# Steuerung.net
KiCad netlist of a schematic drawn in EAGLE
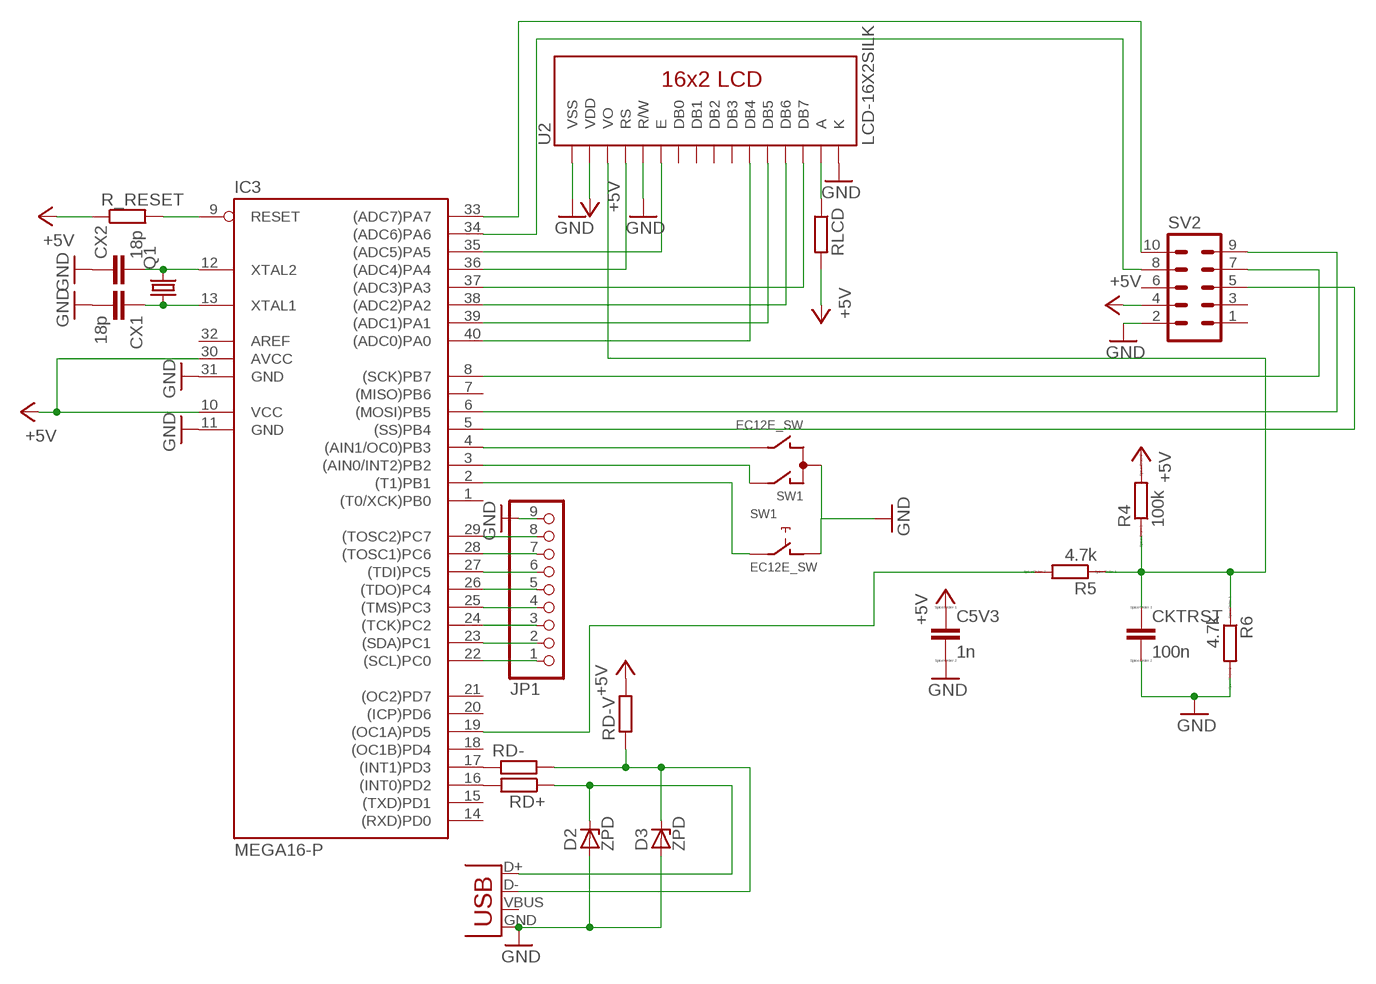
[diagram p0: schematic, sheet 1]

(export (version "E")
  (design (tool "Eeschema 10.0.6"))
  (components
    (comp (ref "C5V3")
      (value "1n")
      (footprint "eagle-import:C1206K")
      (libsource (lib "eagle-import") (part "C-EUC1206K"))
    )
    (comp (ref "CKTRST")
      (value "100n")
      (footprint "eagle-import:C1206K")
      (libsource (lib "eagle-import") (part "C-EUC1206K"))
    )
    (comp (ref "CX1")
      (value "18p")
      (footprint "eagle-import:C2.5-3")
      (libsource (lib "eagle-import") (part "C2,5-3"))
    )
    (comp (ref "CX2")
      (value "18p")
      (footprint "eagle-import:C2.5-3")
      (libsource (lib "eagle-import") (part "C2,5-3"))
    )
    (comp (ref "D2")
      (value "ZPD")
      (footprint "eagle-import:DO35Z10")
      (libsource (lib "eagle-import") (part "ZPD"))
    )
    (comp (ref "D3")
      (value "ZPD")
      (footprint "eagle-import:DO35Z10")
      (libsource (lib "eagle-import") (part "ZPD"))
    )
    (comp (ref "IC3")
      (value "MEGA16-P")
      (footprint "eagle-import:DIL40")
      (fields (field (name "MPN") "ATMEGA16-16PU") (field (name "MF") "ATMEL"))
      (libsource (lib "eagle-import") (part "MEGA16-P"))
    )
    (comp (ref "JP1")
      (value "PINHD-1X9")
      (footprint "eagle-import:1X09")
      (libsource (lib "eagle-import") (part "PINHD-1X9"))
    )
    (comp (ref "JP2")
      (value "USBPTH-VERTICAL")
      (footprint "eagle-import:USB-B-PTH-VERTICAL")
      (libsource (lib "eagle-import") (part "USBPTH-VERTICAL"))
    )
    (comp (ref "Q1")
      (value "CRYSTALHC18U-V")
      (footprint "eagle-import:HC18U-V")
      (libsource (lib "eagle-import") (part "CRYSTALHC18U-V"))
    )
    (comp (ref "R4")
      (value "100k")
      (footprint "eagle-import:R1206W")
      (libsource (lib "eagle-import") (part "resistor_R-EU_R1206W"))
    )
    (comp (ref "R5")
      (value "4.7k")
      (footprint "eagle-import:R1206W")
      (libsource (lib "eagle-import") (part "resistor_R-EU_R1206W"))
    )
    (comp (ref "R6")
      (value "4.7k")
      (footprint "eagle-import:R1206W")
      (libsource (lib "eagle-import") (part "resistor_R-EU_R1206W"))
    )
    (comp (ref "RD+")
      (value "R-EU_0309/12")
      (footprint "eagle-import:0309_12")
      (libsource (lib "eagle-import") (part "R-EU_0309/12"))
    )
    (comp (ref "RD-")
      (value "R-EU_0309/12")
      (footprint "eagle-import:0309_12")
      (libsource (lib "eagle-import") (part "R-EU_0309/12"))
    )
    (comp (ref "RD-V")
      (value "R-EU_0309/12")
      (footprint "eagle-import:0309_12")
      (libsource (lib "eagle-import") (part "R-EU_0309/12"))
    )
    (comp (ref "RLCD")
      (value "R-EU_0309/12")
      (footprint "eagle-import:0309_12")
      (libsource (lib "eagle-import") (part "R-EU_0309/12"))
    )
    (comp (ref "R_RESET")
      (value "R-EU_R1206W")
      (footprint "eagle-import:R1206W")
      (libsource (lib "eagle-import") (part "R-EU_R1206W"))
    )
    (comp (ref "SV2")
      (value "ML10")
      (footprint "eagle-import:ML10")
      (libsource (lib "eagle-import") (part "ML10"))
    )
    (comp (ref "SW1")
      (value "EC12E_SW")
      (footprint "eagle-import:ALPS_EC12E_SW")
      (fields (field (name "MPN") "EC12E2424407"))
      (libsource (lib "eagle-import") (part "EC12E_SW"))
    )
    (comp (ref "U2")
      (value "LCD-16X2SILK")
      (footprint "eagle-import:LCD-16X2")
      (libsource (lib "eagle-import") (part "LCD-16X2SILK"))
    )
  )
  (nets
    (net (code "1") (name "+5V") (class "Default")
      (node (ref "C5V3") (pin "1") (pinfunction "1_1") (pintype "passive"))
      (node (ref "IC3") (pin "10") (pinfunction "VCC_10") (pintype "power_in"))
      (node (ref "IC3") (pin "30") (pinfunction "AVCC_30") (pintype "power_in"))
      (node (ref "R4") (pin "2") (pinfunction "2_2") (pintype "passive"))
      (node (ref "RD-V") (pin "2") (pinfunction "2_2") (pintype "passive"))
      (node (ref "RLCD") (pin "2") (pinfunction "2_2") (pintype "passive"))
      (node (ref "R_RESET") (pin "1") (pinfunction "1_1") (pintype "passive"))
      (node (ref "SV2") (pin "4") (pinfunction "4_4") (pintype "passive"))
      (node (ref "U2") (pin "2") (pinfunction "VDD_2") (pintype "power_in"))
    )
    (net (code "2") (name "GND") (class "Default")
      (node (ref "C5V3") (pin "2") (pinfunction "2_2") (pintype "passive"))
      (node (ref "CKTRST") (pin "2") (pinfunction "2_2") (pintype "passive"))
      (node (ref "CX1") (pin "2") (pinfunction "2_2") (pintype "passive"))
      (node (ref "CX2") (pin "1") (pinfunction "1_1") (pintype "passive"))
      (node (ref "D2") (pin "A") (pinfunction "A_A") (pintype "passive"))
      (node (ref "D3") (pin "A") (pinfunction "A_A") (pintype "passive"))
      (node (ref "IC3") (pin "11") (pinfunction "GND_11") (pintype "power_in"))
      (node (ref "IC3") (pin "31") (pinfunction "GND_31") (pintype "power_in"))
      (node (ref "JP1") (pin "9") (pinfunction "9_9") (pintype "passive"))
      (node (ref "JP2") (pin "GND") (pinfunction "GND_GND") (pintype "bidirectional"))
      (node (ref "R6") (pin "2") (pinfunction "2_2") (pintype "passive"))
      (node (ref "SV2") (pin "2") (pinfunction "2_2") (pintype "passive"))
      (node (ref "SW1") (pin "C") (pinfunction "C_C") (pintype "passive"))
      (node (ref "SW1") (pin "D") (pinfunction "1_D") (pintype "passive"))
      (node (ref "U2") (pin "1") (pinfunction "VSS_1") (pintype "power_in"))
      (node (ref "U2") (pin "16") (pinfunction "K_16") (pintype "power_in"))
      (node (ref "U2") (pin "5") (pinfunction "R/W_5") (pintype "input"))
    )
    (net (code "3") (name "Net-(D2-PadC)") (class "Default")
      (node (ref "D2") (pin "C") (pinfunction "C_C") (pintype "passive"))
      (node (ref "JP2") (pin "D+") (pinfunction "D+_D+") (pintype "bidirectional"))
      (node (ref "RD+") (pin "1") (pinfunction "1_1") (pintype "passive"))
    )
    (net (code "4") (name "Net-(D3-PadC)") (class "Default")
      (node (ref "D3") (pin "C") (pinfunction "C_C") (pintype "passive"))
      (node (ref "JP2") (pin "D-") (pinfunction "D-_D-") (pintype "bidirectional"))
      (node (ref "RD-") (pin "2") (pinfunction "2_2") (pintype "passive"))
      (node (ref "RD-V") (pin "1") (pinfunction "1_1") (pintype "passive"))
    )
    (net (code "5") (name "Net-(IC3-(ADC0)PA0)") (class "Default")
      (node (ref "IC3") (pin "40") (pinfunction "(ADC0)PA0_40") (pintype "bidirectional"))
      (node (ref "U2") (pin "11") (pinfunction "DB4_11") (pintype "bidirectional"))
    )
    (net (code "6") (name "Net-(IC3-(ADC1)PA1)") (class "Default")
      (node (ref "IC3") (pin "39") (pinfunction "(ADC1)PA1_39") (pintype "bidirectional"))
      (node (ref "U2") (pin "12") (pinfunction "DB5_12") (pintype "bidirectional"))
    )
    (net (code "7") (name "Net-(IC3-(ADC2)PA2)") (class "Default")
      (node (ref "IC3") (pin "38") (pinfunction "(ADC2)PA2_38") (pintype "bidirectional"))
      (node (ref "U2") (pin "13") (pinfunction "DB6_13") (pintype "bidirectional"))
    )
    (net (code "8") (name "Net-(IC3-(ADC3)PA3)") (class "Default")
      (node (ref "IC3") (pin "37") (pinfunction "(ADC3)PA3_37") (pintype "bidirectional"))
      (node (ref "U2") (pin "14") (pinfunction "DB7_14") (pintype "bidirectional"))
    )
    (net (code "9") (name "Net-(IC3-(ADC4)PA4)") (class "Default")
      (node (ref "IC3") (pin "36") (pinfunction "(ADC4)PA4_36") (pintype "bidirectional"))
      (node (ref "U2") (pin "4") (pinfunction "RS_4") (pintype "input"))
    )
    (net (code "10") (name "Net-(IC3-(ADC5)PA5)") (class "Default")
      (node (ref "IC3") (pin "35") (pinfunction "(ADC5)PA5_35") (pintype "bidirectional"))
      (node (ref "U2") (pin "6") (pinfunction "E_6") (pintype "input"))
    )
    (net (code "11") (name "Net-(IC3-(ADC6)PA6)") (class "Default")
      (node (ref "IC3") (pin "34") (pinfunction "(ADC6)PA6_34") (pintype "bidirectional"))
      (node (ref "SV2") (pin "8") (pinfunction "8_8") (pintype "passive"))
    )
    (net (code "12") (name "Net-(IC3-(ADC7)PA7)") (class "Default")
      (node (ref "IC3") (pin "33") (pinfunction "(ADC7)PA7_33") (pintype "bidirectional"))
      (node (ref "SV2") (pin "10") (pinfunction "10_10") (pintype "passive"))
    )
    (net (code "13") (name "Net-(IC3-(AIN0{slash}INT2)PB2)") (class "Default")
      (node (ref "IC3") (pin "3") (pinfunction "(AIN0/INT2)PB2_3") (pintype "bidirectional"))
      (node (ref "SW1") (pin "A") (pinfunction "A_A") (pintype "passive"))
    )
    (net (code "14") (name "Net-(IC3-(AIN1{slash}OC0)PB3)") (class "Default")
      (node (ref "IC3") (pin "4") (pinfunction "(AIN1/OC0)PB3_4") (pintype "bidirectional"))
      (node (ref "SW1") (pin "B") (pinfunction "B_B") (pintype "passive"))
    )
    (net (code "15") (name "Net-(IC3-(INT0)PD2)") (class "Default")
      (node (ref "IC3") (pin "16") (pinfunction "(INT0)PD2_16") (pintype "bidirectional"))
      (node (ref "RD+") (pin "2") (pinfunction "2_2") (pintype "passive"))
    )
    (net (code "16") (name "Net-(IC3-(INT1)PD3)") (class "Default")
      (node (ref "IC3") (pin "17") (pinfunction "(INT1)PD3_17") (pintype "bidirectional"))
      (node (ref "RD-") (pin "1") (pinfunction "1_1") (pintype "passive"))
    )
    (net (code "17") (name "Net-(IC3-(MOSI)PB5)") (class "Default")
      (node (ref "IC3") (pin "6") (pinfunction "(MOSI)PB5_6") (pintype "bidirectional"))
      (node (ref "SV2") (pin "9") (pinfunction "9_9") (pintype "passive"))
    )
    (net (code "18") (name "Net-(IC3-(OC1A)PD5)") (class "Default")
      (node (ref "IC3") (pin "19") (pinfunction "(OC1A)PD5_19") (pintype "bidirectional"))
      (node (ref "R5") (pin "2") (pinfunction "2_2") (pintype "passive"))
    )
    (net (code "19") (name "Net-(IC3-(SCK)PB7)") (class "Default")
      (node (ref "IC3") (pin "8") (pinfunction "(SCK)PB7_8") (pintype "bidirectional"))
      (node (ref "SV2") (pin "7") (pinfunction "7_7") (pintype "passive"))
    )
    (net (code "20") (name "Net-(IC3-(SCL)PC0)") (class "Default")
      (node (ref "IC3") (pin "22") (pinfunction "(SCL)PC0_22") (pintype "bidirectional"))
      (node (ref "JP1") (pin "1") (pinfunction "1_1") (pintype "passive"))
    )
    (net (code "21") (name "Net-(IC3-(SDA)PC1)") (class "Default")
      (node (ref "IC3") (pin "23") (pinfunction "(SDA)PC1_23") (pintype "bidirectional"))
      (node (ref "JP1") (pin "2") (pinfunction "2_2") (pintype "passive"))
    )
    (net (code "22") (name "Net-(IC3-(SS)PB4)") (class "Default")
      (node (ref "IC3") (pin "5") (pinfunction "(SS)PB4_5") (pintype "bidirectional"))
      (node (ref "SV2") (pin "5") (pinfunction "5_5") (pintype "passive"))
    )
    (net (code "23") (name "Net-(IC3-(T1)PB1)") (class "Default")
      (node (ref "IC3") (pin "2") (pinfunction "(T1)PB1_2") (pintype "bidirectional"))
      (node (ref "SW1") (pin "E") (pinfunction "2_E") (pintype "passive"))
    )
    (net (code "24") (name "Net-(IC3-(TCK)PC2)") (class "Default")
      (node (ref "IC3") (pin "24") (pinfunction "(TCK)PC2_24") (pintype "bidirectional"))
      (node (ref "JP1") (pin "3") (pinfunction "3_3") (pintype "passive"))
    )
    (net (code "25") (name "Net-(IC3-(TDI)PC5)") (class "Default")
      (node (ref "IC3") (pin "27") (pinfunction "(TDI)PC5_27") (pintype "bidirectional"))
      (node (ref "JP1") (pin "6") (pinfunction "6_6") (pintype "passive"))
    )
    (net (code "26") (name "Net-(IC3-(TDO)PC4)") (class "Default")
      (node (ref "IC3") (pin "26") (pinfunction "(TDO)PC4_26") (pintype "bidirectional"))
      (node (ref "JP1") (pin "5") (pinfunction "5_5") (pintype "passive"))
    )
    (net (code "27") (name "Net-(IC3-(TMS)PC3)") (class "Default")
      (node (ref "IC3") (pin "25") (pinfunction "(TMS)PC3_25") (pintype "bidirectional"))
      (node (ref "JP1") (pin "4") (pinfunction "4_4") (pintype "passive"))
    )
    (net (code "28") (name "Net-(IC3-(TOSC1)PC6)") (class "Default")
      (node (ref "IC3") (pin "28") (pinfunction "(TOSC1)PC6_28") (pintype "bidirectional"))
      (node (ref "JP1") (pin "7") (pinfunction "7_7") (pintype "passive"))
    )
    (net (code "29") (name "Net-(IC3-(TOSC2)PC7)") (class "Default")
      (node (ref "IC3") (pin "29") (pinfunction "(TOSC2)PC7_29") (pintype "bidirectional"))
      (node (ref "JP1") (pin "8") (pinfunction "8_8") (pintype "passive"))
    )
    (net (code "30") (name "Net-(IC3-RESET)") (class "Default")
      (node (ref "IC3") (pin "9") (pinfunction "RESET_9") (pintype "input"))
      (node (ref "R_RESET") (pin "2") (pinfunction "2_2") (pintype "passive"))
    )
    (net (code "31") (name "Net-(IC3-XTAL1)") (class "Default")
      (node (ref "CX1") (pin "1") (pinfunction "1_1") (pintype "passive"))
      (node (ref "IC3") (pin "13") (pinfunction "XTAL1_13") (pintype "bidirectional"))
      (node (ref "Q1") (pin "1") (pinfunction "1_1") (pintype "passive"))
    )
    (net (code "32") (name "Net-(IC3-XTAL2)") (class "Default")
      (node (ref "CX2") (pin "2") (pinfunction "2_2") (pintype "passive"))
      (node (ref "IC3") (pin "12") (pinfunction "XTAL2_12") (pintype "bidirectional"))
      (node (ref "Q1") (pin "2") (pinfunction "2_2") (pintype "passive"))
    )
    (net (code "33") (name "Net-(U2-A)") (class "Default")
      (node (ref "RLCD") (pin "1") (pinfunction "1_1") (pintype "passive"))
      (node (ref "U2") (pin "15") (pinfunction "A_15") (pintype "power_in"))
    )
    (net (code "34") (name "Net-(U2-VO)") (class "Default")
      (node (ref "CKTRST") (pin "1") (pinfunction "1_1") (pintype "passive"))
      (node (ref "R4") (pin "1") (pinfunction "1_1") (pintype "passive"))
      (node (ref "R5") (pin "1") (pinfunction "1_1") (pintype "passive"))
      (node (ref "R6") (pin "1") (pinfunction "1_1") (pintype "passive"))
      (node (ref "U2") (pin "3") (pinfunction "VO_3") (pintype "bidirectional"))
    )
    (net (code "35") (name "unconnected-(IC3-(ICP)PD6-Pad20)") (class "Default")
      (node (ref "IC3") (pin "20") (pinfunction "(ICP)PD6_20") (pintype "bidirectional"))
    )
    (net (code "36") (name "unconnected-(IC3-(MISO)PB6-Pad7)") (class "Default")
      (node (ref "IC3") (pin "7") (pinfunction "(MISO)PB6_7") (pintype "bidirectional"))
    )
    (net (code "37") (name "unconnected-(IC3-(OC1B)PD4-Pad18)") (class "Default")
      (node (ref "IC3") (pin "18") (pinfunction "(OC1B)PD4_18") (pintype "bidirectional"))
    )
    (net (code "38") (name "unconnected-(IC3-(OC2)PD7-Pad21)") (class "Default")
      (node (ref "IC3") (pin "21") (pinfunction "(OC2)PD7_21") (pintype "bidirectional"))
    )
    (net (code "39") (name "unconnected-(IC3-(RXD)PD0-Pad14)") (class "Default")
      (node (ref "IC3") (pin "14") (pinfunction "(RXD)PD0_14") (pintype "bidirectional"))
    )
    (net (code "40") (name "unconnected-(IC3-(T0{slash}XCK)PB0-Pad1)") (class "Default")
      (node (ref "IC3") (pin "1") (pinfunction "(T0/XCK)PB0_1") (pintype "bidirectional"))
    )
    (net (code "41") (name "unconnected-(IC3-(TXD)PD1-Pad15)") (class "Default")
      (node (ref "IC3") (pin "15") (pinfunction "(TXD)PD1_15") (pintype "bidirectional"))
    )
    (net (code "42") (name "unconnected-(IC3-AREF-Pad32)") (class "Default")
      (node (ref "IC3") (pin "32") (pinfunction "AREF_32") (pintype "passive"))
    )
    (net (code "43") (name "unconnected-(JP2-PadVBUS)") (class "Default")
      (node (ref "JP2") (pin "VBUS") (pinfunction "VBUS_VBUS") (pintype "bidirectional"))
    )
    (net (code "44") (name "unconnected-(SV2-Pad1)") (class "Default")
      (node (ref "SV2") (pin "1") (pinfunction "1_1") (pintype "passive"))
    )
    (net (code "45") (name "unconnected-(SV2-Pad3)") (class "Default")
      (node (ref "SV2") (pin "3") (pinfunction "3_3") (pintype "passive"))
    )
    (net (code "46") (name "unconnected-(SV2-Pad6)") (class "Default")
      (node (ref "SV2") (pin "6") (pinfunction "6_6") (pintype "passive"))
    )
    (net (code "47") (name "unconnected-(U2-DB0-Pad7)") (class "Default")
      (node (ref "U2") (pin "7") (pinfunction "DB0_7") (pintype "bidirectional"))
    )
    (net (code "48") (name "unconnected-(U2-DB1-Pad8)") (class "Default")
      (node (ref "U2") (pin "8") (pinfunction "DB1_8") (pintype "bidirectional"))
    )
    (net (code "49") (name "unconnected-(U2-DB2-Pad9)") (class "Default")
      (node (ref "U2") (pin "9") (pinfunction "DB2_9") (pintype "bidirectional"))
    )
    (net (code "50") (name "unconnected-(U2-DB3-Pad10)") (class "Default")
      (node (ref "U2") (pin "10") (pinfunction "DB3_10") (pintype "bidirectional"))
    )
  )
)
